# 1A20J8_1A21J10_A.net
KiCad netlist of a schematic drawn in Altium Designer
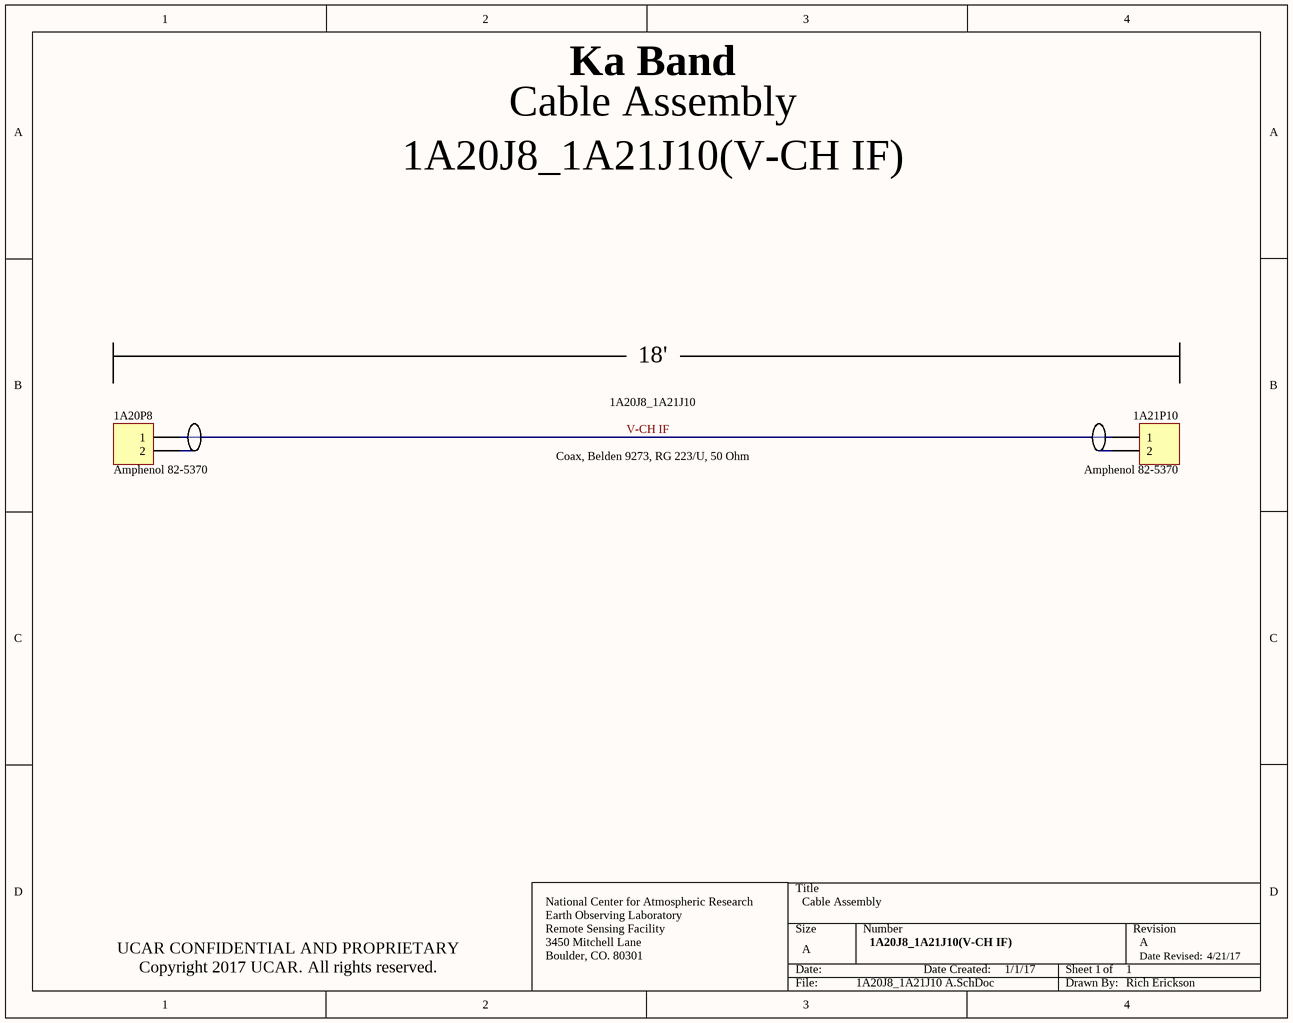
[diagram p0: 1A20J8_1A21J10 A.SchDoc]

(export (version "E")
  (design (tool "Eeschema 10.0.6"))
  (components
    (comp (ref "1A20P8")
      (value "Amphenol 82-5370")
      (footprint "HDR1X2")
      (description "Header, 2-Pin")
      (fields (field (name "PUBLISHER") "Altium Limited"))
      (libsource (lib "Miscellaneous Connectors") (part "Header 2"))
    )
    (comp (ref "1A21P10")
      (value "Amphenol 82-5370")
      (footprint "HDR1X2")
      (description "Header, 2-Pin")
      (fields (field (name "PUBLISHER") "Altium Limited"))
      (libsource (lib "") (part "Header 2_1"))
    )
  )
  (nets
    (net (code "1") (name "/V-CH IF") (class "Default")
      (node (ref "1A20P8") (pin "1") (pinfunction "1_1") (pintype "passive"))
      (node (ref "1A21P10") (pin "1") (pinfunction "1_1") (pintype "passive"))
    )
    (net (code "2") (name "unconnected-(1A20P8-Pad2)") (class "Default")
      (node (ref "1A20P8") (pin "2") (pinfunction "2_2") (pintype "passive"))
    )
    (net (code "3") (name "unconnected-(1A21P10-Pad2)") (class "Default")
      (node (ref "1A21P10") (pin "2") (pinfunction "2_2") (pintype "passive"))
    )
  )
)
